# MidiWah.net
KiCad netlist of a schematic drawn in EAGLE
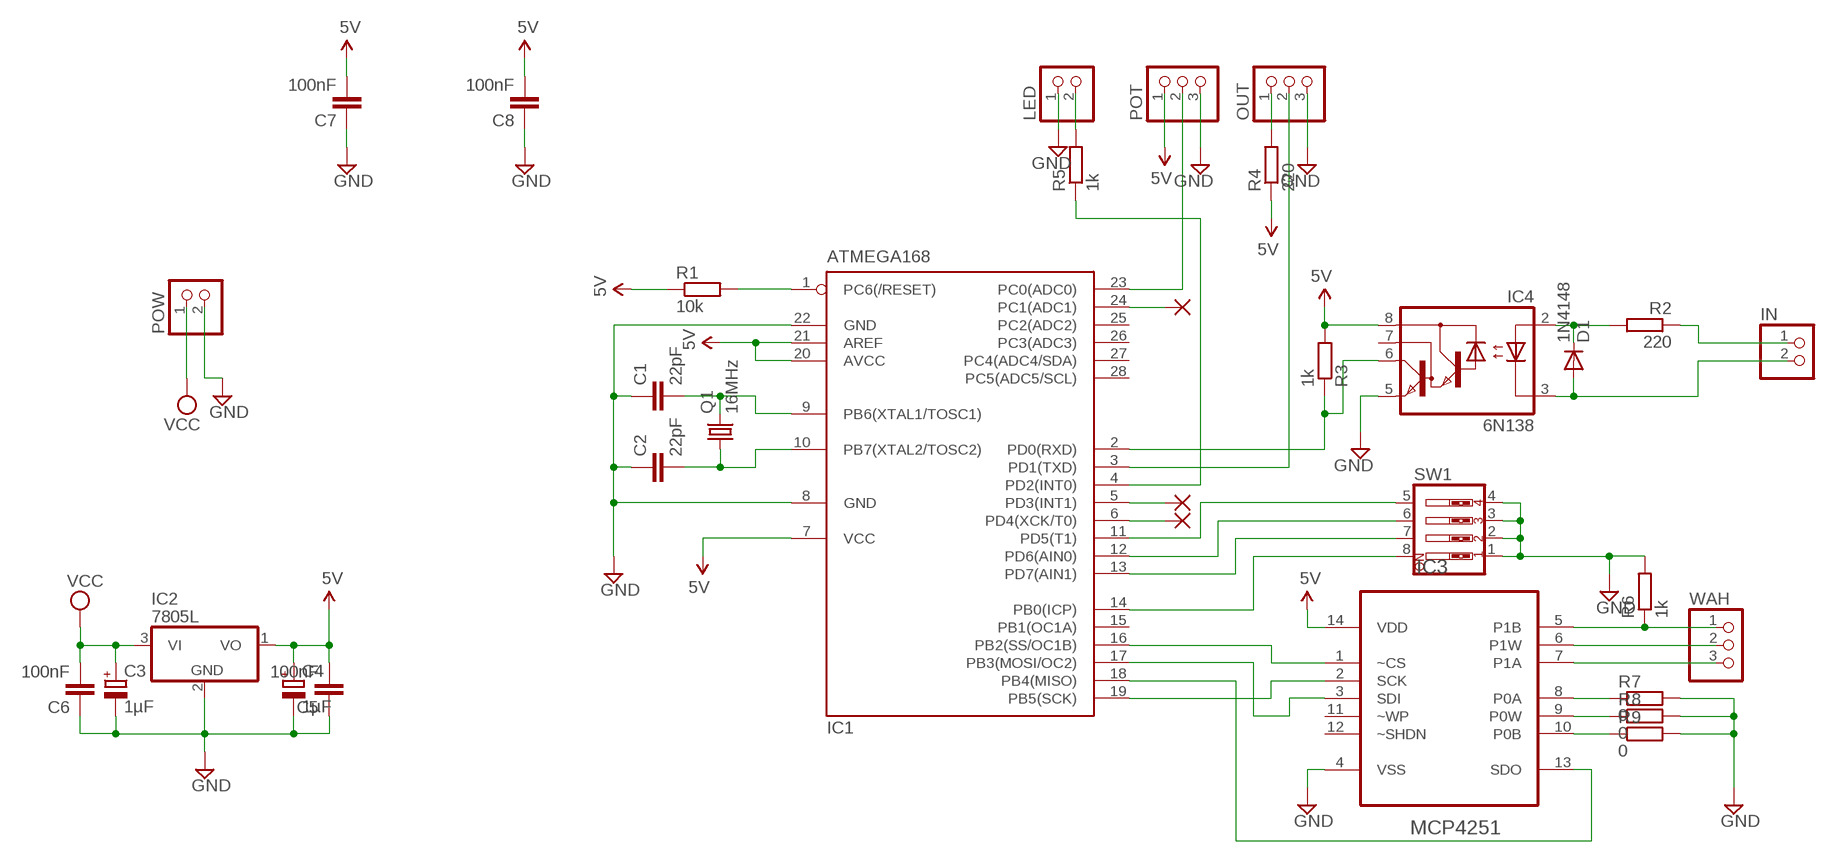
[diagram p0: schematic, sheet 1]

(export (version "E")
  (design (tool "Eeschema 10.0.6"))
  (components
    (comp (ref "C1")
      (value "22pF")
      (footprint "eagle-import:C025-024X044")
      (libsource (lib "eagle-import") (part "C-EU025-024X044"))
    )
    (comp (ref "C2")
      (value "22pF")
      (footprint "eagle-import:C025-024X044")
      (libsource (lib "eagle-import") (part "C-EU025-024X044"))
    )
    (comp (ref "C3")
      (value "1µF")
      (footprint "eagle-import:E2,5-5")
      (libsource (lib "eagle-import") (part "CPOL-EUE2.5-5"))
    )
    (comp (ref "C4")
      (value "1µF")
      (footprint "eagle-import:E2,5-5")
      (libsource (lib "eagle-import") (part "CPOL-EUE2.5-5"))
    )
    (comp (ref "C5")
      (value "100nF")
      (footprint "eagle-import:C025-024X044")
      (libsource (lib "eagle-import") (part "C-EU025-024X044"))
    )
    (comp (ref "C6")
      (value "100nF")
      (footprint "eagle-import:C025-024X044")
      (libsource (lib "eagle-import") (part "C-EU025-024X044"))
    )
    (comp (ref "C7")
      (value "100nF")
      (footprint "eagle-import:C025-024X044")
      (libsource (lib "eagle-import") (part "C-EU025-024X044"))
    )
    (comp (ref "C8")
      (value "100nF")
      (footprint "eagle-import:C025-024X044")
      (libsource (lib "eagle-import") (part "C-EU025-024X044"))
    )
    (comp (ref "D1")
      (value "1N4148")
      (footprint "eagle-import:DO35-7")
      (libsource (lib "eagle-import") (part "1N4148DO35-7"))
    )
    (comp (ref "IC1")
      (value "ATMEGA168")
      (footprint "eagle-import:DIL28-3")
      (libsource (lib "eagle-import") (part "MEGA8-P"))
    )
    (comp (ref "IC2")
      (value "7805L")
      (footprint "eagle-import:TO92")
      (libsource (lib "eagle-import") (part "78L05"))
    )
    (comp (ref "IC3")
      (value "MCP4251")
      (footprint "eagle-import:DIP254P762X533-14")
      (fields (field (name "MPN") "MCP4251-104E/P"))
      (libsource (lib "eagle-import") (part "MCP4251-104E/P"))
    )
    (comp (ref "IC4")
      (value "6N138")
      (footprint "eagle-import:DIL08")
      (fields (field (name "MF") "VISHAY/TELEFUNKEN"))
      (libsource (lib "eagle-import") (part "6N138"))
    )
    (comp (ref "IN")
      (value "PINHD-1X2")
      (footprint "eagle-import:1X02")
      (libsource (lib "eagle-import") (part "PINHD-1X2"))
    )
    (comp (ref "LED")
      (value "PINHD-1X2")
      (footprint "eagle-import:1X02")
      (libsource (lib "eagle-import") (part "PINHD-1X2"))
    )
    (comp (ref "OUT")
      (value "PINHD-1X3")
      (footprint "eagle-import:1X03")
      (libsource (lib "eagle-import") (part "PINHD-1X3"))
    )
    (comp (ref "PAD1")
      (value "WIREPAD1,6/0,8")
      (footprint "eagle-import:1,6_0,8")
      (libsource (lib "eagle-import") (part "WIREPAD1,6/0,8"))
    )
    (comp (ref "PAD2")
      (value "WIREPAD1,6/0,8")
      (footprint "eagle-import:1,6_0,8")
      (libsource (lib "eagle-import") (part "WIREPAD1,6/0,8"))
    )
    (comp (ref "PAD3")
      (value "WIREPAD1,6/0,8")
      (footprint "eagle-import:1,6_0,8")
      (libsource (lib "eagle-import") (part "WIREPAD1,6/0,8"))
    )
    (comp (ref "POT")
      (value "PINHD-1X3")
      (footprint "eagle-import:1X03")
      (libsource (lib "eagle-import") (part "PINHD-1X3"))
    )
    (comp (ref "POW")
      (value "PINHD-1X2")
      (footprint "eagle-import:1X02")
      (libsource (lib "eagle-import") (part "PINHD-1X2"))
    )
    (comp (ref "Q1")
      (value "16MHz")
      (footprint "eagle-import:HC49_S")
      (libsource (lib "eagle-import") (part "CRYSTALHC49S"))
    )
    (comp (ref "R1")
      (value "10k")
      (footprint "eagle-import:0204_7")
      (libsource (lib "eagle-import") (part "R-EU_0204/7"))
    )
    (comp (ref "R2")
      (value "220")
      (footprint "eagle-import:0204_7")
      (libsource (lib "eagle-import") (part "R-EU_0204/7"))
    )
    (comp (ref "R3")
      (value "1k")
      (footprint "eagle-import:0204_7")
      (libsource (lib "eagle-import") (part "R-EU_0204/7"))
    )
    (comp (ref "R4")
      (value "220")
      (footprint "eagle-import:0204_7")
      (libsource (lib "eagle-import") (part "R-EU_0204/7"))
    )
    (comp (ref "R5")
      (value "1k")
      (footprint "eagle-import:0204_7")
      (libsource (lib "eagle-import") (part "R-EU_0204/7"))
    )
    (comp (ref "R6")
      (value "1k")
      (footprint "eagle-import:0204V")
      (libsource (lib "eagle-import") (part "R-EU_0204/2V"))
    )
    (comp (ref "R7")
      (value "0")
      (footprint "eagle-import:M0805")
      (libsource (lib "eagle-import") (part "R-EU_M0805"))
    )
    (comp (ref "R8")
      (value "0")
      (footprint "eagle-import:M0805")
      (libsource (lib "eagle-import") (part "R-EU_M0805"))
    )
    (comp (ref "R9")
      (value "0")
      (footprint "eagle-import:M0805")
      (libsource (lib "eagle-import") (part "R-EU_M0805"))
    )
    (comp (ref "SW1")
      (value "SW_DIP-4")
      (footprint "eagle-import:EDG-04")
      (libsource (lib "eagle-import") (part "SW_DIP-4"))
    )
    (comp (ref "WAH")
      (value "PINHD-1X3")
      (footprint "eagle-import:1X03")
      (libsource (lib "eagle-import") (part "PINHD-1X3"))
    )
  )
  (nets
    (net (code "1") (name "5V") (class "Default")
      (node (ref "C4") (pin "+") (pinfunction "+_+") (pintype "passive"))
      (node (ref "C5") (pin "2") (pinfunction "2_2") (pintype "passive"))
      (node (ref "C7") (pin "2") (pinfunction "2_2") (pintype "passive"))
      (node (ref "C8") (pin "2") (pinfunction "2_2") (pintype "passive"))
      (node (ref "IC1") (pin "20") (pinfunction "AVCC_20") (pintype "power_in"))
      (node (ref "IC1") (pin "21") (pinfunction "AREF_21") (pintype "passive"))
      (node (ref "IC1") (pin "7") (pinfunction "VCC_7") (pintype "power_in"))
      (node (ref "IC2") (pin "1") (pinfunction "VO_1") (pintype "passive"))
      (node (ref "IC3") (pin "14") (pinfunction "VDD_14") (pintype "power_in"))
      (node (ref "IC4") (pin "8") (pinfunction "VCC_8") (pintype "passive"))
      (node (ref "POT") (pin "1") (pinfunction "1_1") (pintype "passive"))
      (node (ref "R1") (pin "1") (pinfunction "1_1") (pintype "passive"))
      (node (ref "R3") (pin "2") (pinfunction "2_2") (pintype "passive"))
      (node (ref "R4") (pin "1") (pinfunction "1_1") (pintype "passive"))
    )
    (net (code "2") (name "GND") (class "Default")
      (node (ref "C1") (pin "1") (pinfunction "1_1") (pintype "passive"))
      (node (ref "C2") (pin "1") (pinfunction "1_1") (pintype "passive"))
      (node (ref "C3") (pin "-") (pinfunction "-_-") (pintype "passive"))
      (node (ref "C4") (pin "-") (pinfunction "-_-") (pintype "passive"))
      (node (ref "C5") (pin "1") (pinfunction "1_1") (pintype "passive"))
      (node (ref "C6") (pin "1") (pinfunction "1_1") (pintype "passive"))
      (node (ref "C7") (pin "1") (pinfunction "1_1") (pintype "passive"))
      (node (ref "C8") (pin "1") (pinfunction "1_1") (pintype "passive"))
      (node (ref "IC1") (pin "22") (pinfunction "GND_22") (pintype "power_in"))
      (node (ref "IC1") (pin "8") (pinfunction "GND_8") (pintype "power_in"))
      (node (ref "IC2") (pin "2") (pinfunction "GND_2") (pintype "passive"))
      (node (ref "IC3") (pin "4") (pinfunction "VSS_4") (pintype "power_in"))
      (node (ref "IC4") (pin "5") (pinfunction "GND_5") (pintype "passive"))
      (node (ref "LED") (pin "1") (pinfunction "1_1") (pintype "passive"))
      (node (ref "OUT") (pin "3") (pinfunction "3_3") (pintype "passive"))
      (node (ref "POT") (pin "3") (pinfunction "3_3") (pintype "passive"))
      (node (ref "POW") (pin "2") (pinfunction "2_2") (pintype "passive"))
      (node (ref "R6") (pin "2") (pinfunction "2_2") (pintype "passive"))
      (node (ref "R7") (pin "2") (pinfunction "2_2") (pintype "passive"))
      (node (ref "R8") (pin "2") (pinfunction "2_2") (pintype "passive"))
      (node (ref "R9") (pin "2") (pinfunction "2_2") (pintype "passive"))
      (node (ref "SW1") (pin "1") (pinfunction "1_1") (pintype "passive"))
      (node (ref "SW1") (pin "2") (pinfunction "2_2") (pintype "passive"))
      (node (ref "SW1") (pin "3") (pinfunction "3_3") (pintype "passive"))
      (node (ref "SW1") (pin "4") (pinfunction "4_4") (pintype "passive"))
    )
    (net (code "3") (name "Net-(IC1-PB0(ICP))") (class "Default")
      (node (ref "IC1") (pin "14") (pinfunction "PB0(ICP)_14") (pintype "bidirectional"))
      (node (ref "SW1") (pin "8") (pinfunction "8_8") (pintype "passive"))
    )
    (net (code "4") (name "Net-(IC1-PB2(SS{slash}OC1B))") (class "Default")
      (node (ref "IC1") (pin "16") (pinfunction "PB2(SS/OC1B)_16") (pintype "bidirectional"))
      (node (ref "IC3") (pin "1") (pinfunction "~{CS}_1") (pintype "input"))
    )
    (net (code "5") (name "Net-(IC1-PB3(MOSI{slash}OC2))") (class "Default")
      (node (ref "IC1") (pin "17") (pinfunction "PB3(MOSI/OC2)_17") (pintype "bidirectional"))
      (node (ref "IC3") (pin "3") (pinfunction "SDI_3") (pintype "input"))
    )
    (net (code "6") (name "Net-(IC1-PB4(MISO))") (class "Default")
      (node (ref "IC1") (pin "18") (pinfunction "PB4(MISO)_18") (pintype "bidirectional"))
      (node (ref "IC3") (pin "13") (pinfunction "SDO_13") (pintype "output"))
    )
    (net (code "7") (name "Net-(IC1-PB5(SCK))") (class "Default")
      (node (ref "IC1") (pin "19") (pinfunction "PB5(SCK)_19") (pintype "bidirectional"))
      (node (ref "IC3") (pin "2") (pinfunction "SCK_2") (pintype "input"))
    )
    (net (code "8") (name "Net-(IC1-PB6(XTAL1{slash}TOSC1))") (class "Default")
      (node (ref "C1") (pin "2") (pinfunction "2_2") (pintype "passive"))
      (node (ref "IC1") (pin "9") (pinfunction "PB6(XTAL1/TOSC1)_9") (pintype "bidirectional"))
      (node (ref "Q1") (pin "2") (pinfunction "2_2") (pintype "passive"))
    )
    (net (code "9") (name "Net-(IC1-PB7(XTAL2{slash}TOSC2))") (class "Default")
      (node (ref "C2") (pin "2") (pinfunction "2_2") (pintype "passive"))
      (node (ref "IC1") (pin "10") (pinfunction "PB7(XTAL2/TOSC2)_10") (pintype "bidirectional"))
      (node (ref "Q1") (pin "1") (pinfunction "1_1") (pintype "passive"))
    )
    (net (code "10") (name "Net-(IC1-PC0(ADC0))") (class "Default")
      (node (ref "IC1") (pin "23") (pinfunction "PC0(ADC0)_23") (pintype "bidirectional"))
      (node (ref "POT") (pin "2") (pinfunction "2_2") (pintype "passive"))
    )
    (net (code "11") (name "Net-(IC1-PC1(ADC1))") (class "Default")
      (node (ref "IC1") (pin "24") (pinfunction "PC1(ADC1)_24") (pintype "bidirectional"))
      (node (ref "PAD1") (pin "1") (pinfunction "P_1") (pintype "passive"))
    )
    (net (code "12") (name "Net-(IC1-PC6({slash}RESET))") (class "Default")
      (node (ref "IC1") (pin "1") (pinfunction "PC6(/RESET)_1") (pintype "bidirectional"))
      (node (ref "R1") (pin "2") (pinfunction "2_2") (pintype "passive"))
    )
    (net (code "13") (name "Net-(IC1-PD0(RXD))") (class "Default")
      (node (ref "IC1") (pin "2") (pinfunction "PD0(RXD)_2") (pintype "bidirectional"))
      (node (ref "IC4") (pin "6") (pinfunction "VO_6") (pintype "passive"))
      (node (ref "R3") (pin "1") (pinfunction "1_1") (pintype "passive"))
    )
    (net (code "14") (name "Net-(IC1-PD1(TXD))") (class "Default")
      (node (ref "IC1") (pin "3") (pinfunction "PD1(TXD)_3") (pintype "bidirectional"))
      (node (ref "OUT") (pin "2") (pinfunction "2_2") (pintype "passive"))
    )
    (net (code "15") (name "Net-(IC1-PD2(INT0))") (class "Default")
      (node (ref "IC1") (pin "4") (pinfunction "PD2(INT0)_4") (pintype "bidirectional"))
      (node (ref "R5") (pin "1") (pinfunction "1_1") (pintype "passive"))
    )
    (net (code "16") (name "Net-(IC1-PD3(INT1))") (class "Default")
      (node (ref "IC1") (pin "5") (pinfunction "PD3(INT1)_5") (pintype "bidirectional"))
      (node (ref "PAD2") (pin "1") (pinfunction "P_1") (pintype "passive"))
    )
    (net (code "17") (name "Net-(IC1-PD4(XCK{slash}T0))") (class "Default")
      (node (ref "IC1") (pin "6") (pinfunction "PD4(XCK/T0)_6") (pintype "bidirectional"))
      (node (ref "PAD3") (pin "1") (pinfunction "P_1") (pintype "passive"))
    )
    (net (code "18") (name "Net-(IC1-PD5(T1))") (class "Default")
      (node (ref "IC1") (pin "11") (pinfunction "PD5(T1)_11") (pintype "bidirectional"))
      (node (ref "SW1") (pin "5") (pinfunction "5_5") (pintype "passive"))
    )
    (net (code "19") (name "Net-(IC1-PD6(AIN0))") (class "Default")
      (node (ref "IC1") (pin "12") (pinfunction "PD6(AIN0)_12") (pintype "bidirectional"))
      (node (ref "SW1") (pin "6") (pinfunction "6_6") (pintype "passive"))
    )
    (net (code "20") (name "Net-(IC1-PD7(AIN1))") (class "Default")
      (node (ref "IC1") (pin "13") (pinfunction "PD7(AIN1)_13") (pintype "bidirectional"))
      (node (ref "SW1") (pin "7") (pinfunction "7_7") (pintype "passive"))
    )
    (net (code "21") (name "Net-(IC3-P0A)") (class "Default")
      (node (ref "IC3") (pin "8") (pinfunction "P0A_8") (pintype "passive"))
      (node (ref "R7") (pin "1") (pinfunction "1_1") (pintype "passive"))
    )
    (net (code "22") (name "Net-(IC3-P0B)") (class "Default")
      (node (ref "IC3") (pin "10") (pinfunction "P0B_10") (pintype "passive"))
      (node (ref "R9") (pin "1") (pinfunction "1_1") (pintype "passive"))
    )
    (net (code "23") (name "Net-(IC3-P0W)") (class "Default")
      (node (ref "IC3") (pin "9") (pinfunction "P0W_9") (pintype "passive"))
      (node (ref "R8") (pin "1") (pinfunction "1_1") (pintype "passive"))
    )
    (net (code "24") (name "Net-(IC3-P1A)") (class "Default")
      (node (ref "IC3") (pin "7") (pinfunction "P1A_7") (pintype "passive"))
      (node (ref "WAH") (pin "3") (pinfunction "3_3") (pintype "passive"))
    )
    (net (code "25") (name "Net-(IC3-P1B)") (class "Default")
      (node (ref "IC3") (pin "5") (pinfunction "P1B_5") (pintype "passive"))
      (node (ref "R6") (pin "1") (pinfunction "1_1") (pintype "passive"))
      (node (ref "WAH") (pin "1") (pinfunction "1_1") (pintype "passive"))
    )
    (net (code "26") (name "Net-(IC3-P1W)") (class "Default")
      (node (ref "IC3") (pin "6") (pinfunction "P1W_6") (pintype "passive"))
      (node (ref "WAH") (pin "2") (pinfunction "2_2") (pintype "passive"))
    )
    (net (code "27") (name "Net-(IC4-A)") (class "Default")
      (node (ref "D1") (pin "C") (pinfunction "C_C") (pintype "passive"))
      (node (ref "IC4") (pin "2") (pinfunction "A_2") (pintype "passive"))
      (node (ref "R2") (pin "2") (pinfunction "2_2") (pintype "passive"))
    )
    (net (code "28") (name "Net-(IC4-C)") (class "Default")
      (node (ref "D1") (pin "A") (pinfunction "A_A") (pintype "passive"))
      (node (ref "IC4") (pin "3") (pinfunction "C_3") (pintype "passive"))
      (node (ref "IN") (pin "2") (pinfunction "2_2") (pintype "passive"))
    )
    (net (code "29") (name "Net-(IN-Pad1)") (class "Default")
      (node (ref "IN") (pin "1") (pinfunction "1_1") (pintype "passive"))
      (node (ref "R2") (pin "1") (pinfunction "1_1") (pintype "passive"))
    )
    (net (code "30") (name "Net-(LED-Pad2)") (class "Default")
      (node (ref "LED") (pin "2") (pinfunction "2_2") (pintype "passive"))
      (node (ref "R5") (pin "2") (pinfunction "2_2") (pintype "passive"))
    )
    (net (code "31") (name "Net-(OUT-Pad1)") (class "Default")
      (node (ref "OUT") (pin "1") (pinfunction "1_1") (pintype "passive"))
      (node (ref "R4") (pin "2") (pinfunction "2_2") (pintype "passive"))
    )
    (net (code "32") (name "VCC") (class "Default")
      (node (ref "C3") (pin "+") (pinfunction "+_+") (pintype "passive"))
      (node (ref "C6") (pin "2") (pinfunction "2_2") (pintype "passive"))
      (node (ref "IC2") (pin "3") (pinfunction "VI_3") (pintype "input"))
      (node (ref "POW") (pin "1") (pinfunction "1_1") (pintype "passive"))
    )
    (net (code "33") (name "unconnected-(IC1-PB1(OC1A)-Pad15)") (class "Default")
      (node (ref "IC1") (pin "15") (pinfunction "PB1(OC1A)_15") (pintype "bidirectional"))
    )
    (net (code "34") (name "unconnected-(IC1-PC2(ADC2)-Pad25)") (class "Default")
      (node (ref "IC1") (pin "25") (pinfunction "PC2(ADC2)_25") (pintype "bidirectional"))
    )
    (net (code "35") (name "unconnected-(IC1-PC3(ADC3)-Pad26)") (class "Default")
      (node (ref "IC1") (pin "26") (pinfunction "PC3(ADC3)_26") (pintype "bidirectional"))
    )
    (net (code "36") (name "unconnected-(IC1-PC4(ADC4{slash}SDA)-Pad27)") (class "Default")
      (node (ref "IC1") (pin "27") (pinfunction "PC4(ADC4/SDA)_27") (pintype "bidirectional"))
    )
    (net (code "37") (name "unconnected-(IC1-PC5(ADC5{slash}SCL)-Pad28)") (class "Default")
      (node (ref "IC1") (pin "28") (pinfunction "PC5(ADC5/SCL)_28") (pintype "bidirectional"))
    )
    (net (code "38") (name "unconnected-(IC3-~{SHDN}-Pad12)") (class "Default")
      (node (ref "IC3") (pin "12") (pinfunction "~{SHDN}_12") (pintype "input"))
    )
    (net (code "39") (name "unconnected-(IC3-~{WP}-Pad11)") (class "Default")
      (node (ref "IC3") (pin "11") (pinfunction "~{WP}_11") (pintype "input"))
    )
    (net (code "40") (name "unconnected-(IC4-VB-Pad7)") (class "Default")
      (node (ref "IC4") (pin "7") (pinfunction "VB_7") (pintype "passive"))
    )
  )
)
